# MB_Control.net
KiCad netlist of a schematic drawn in Altium Designer
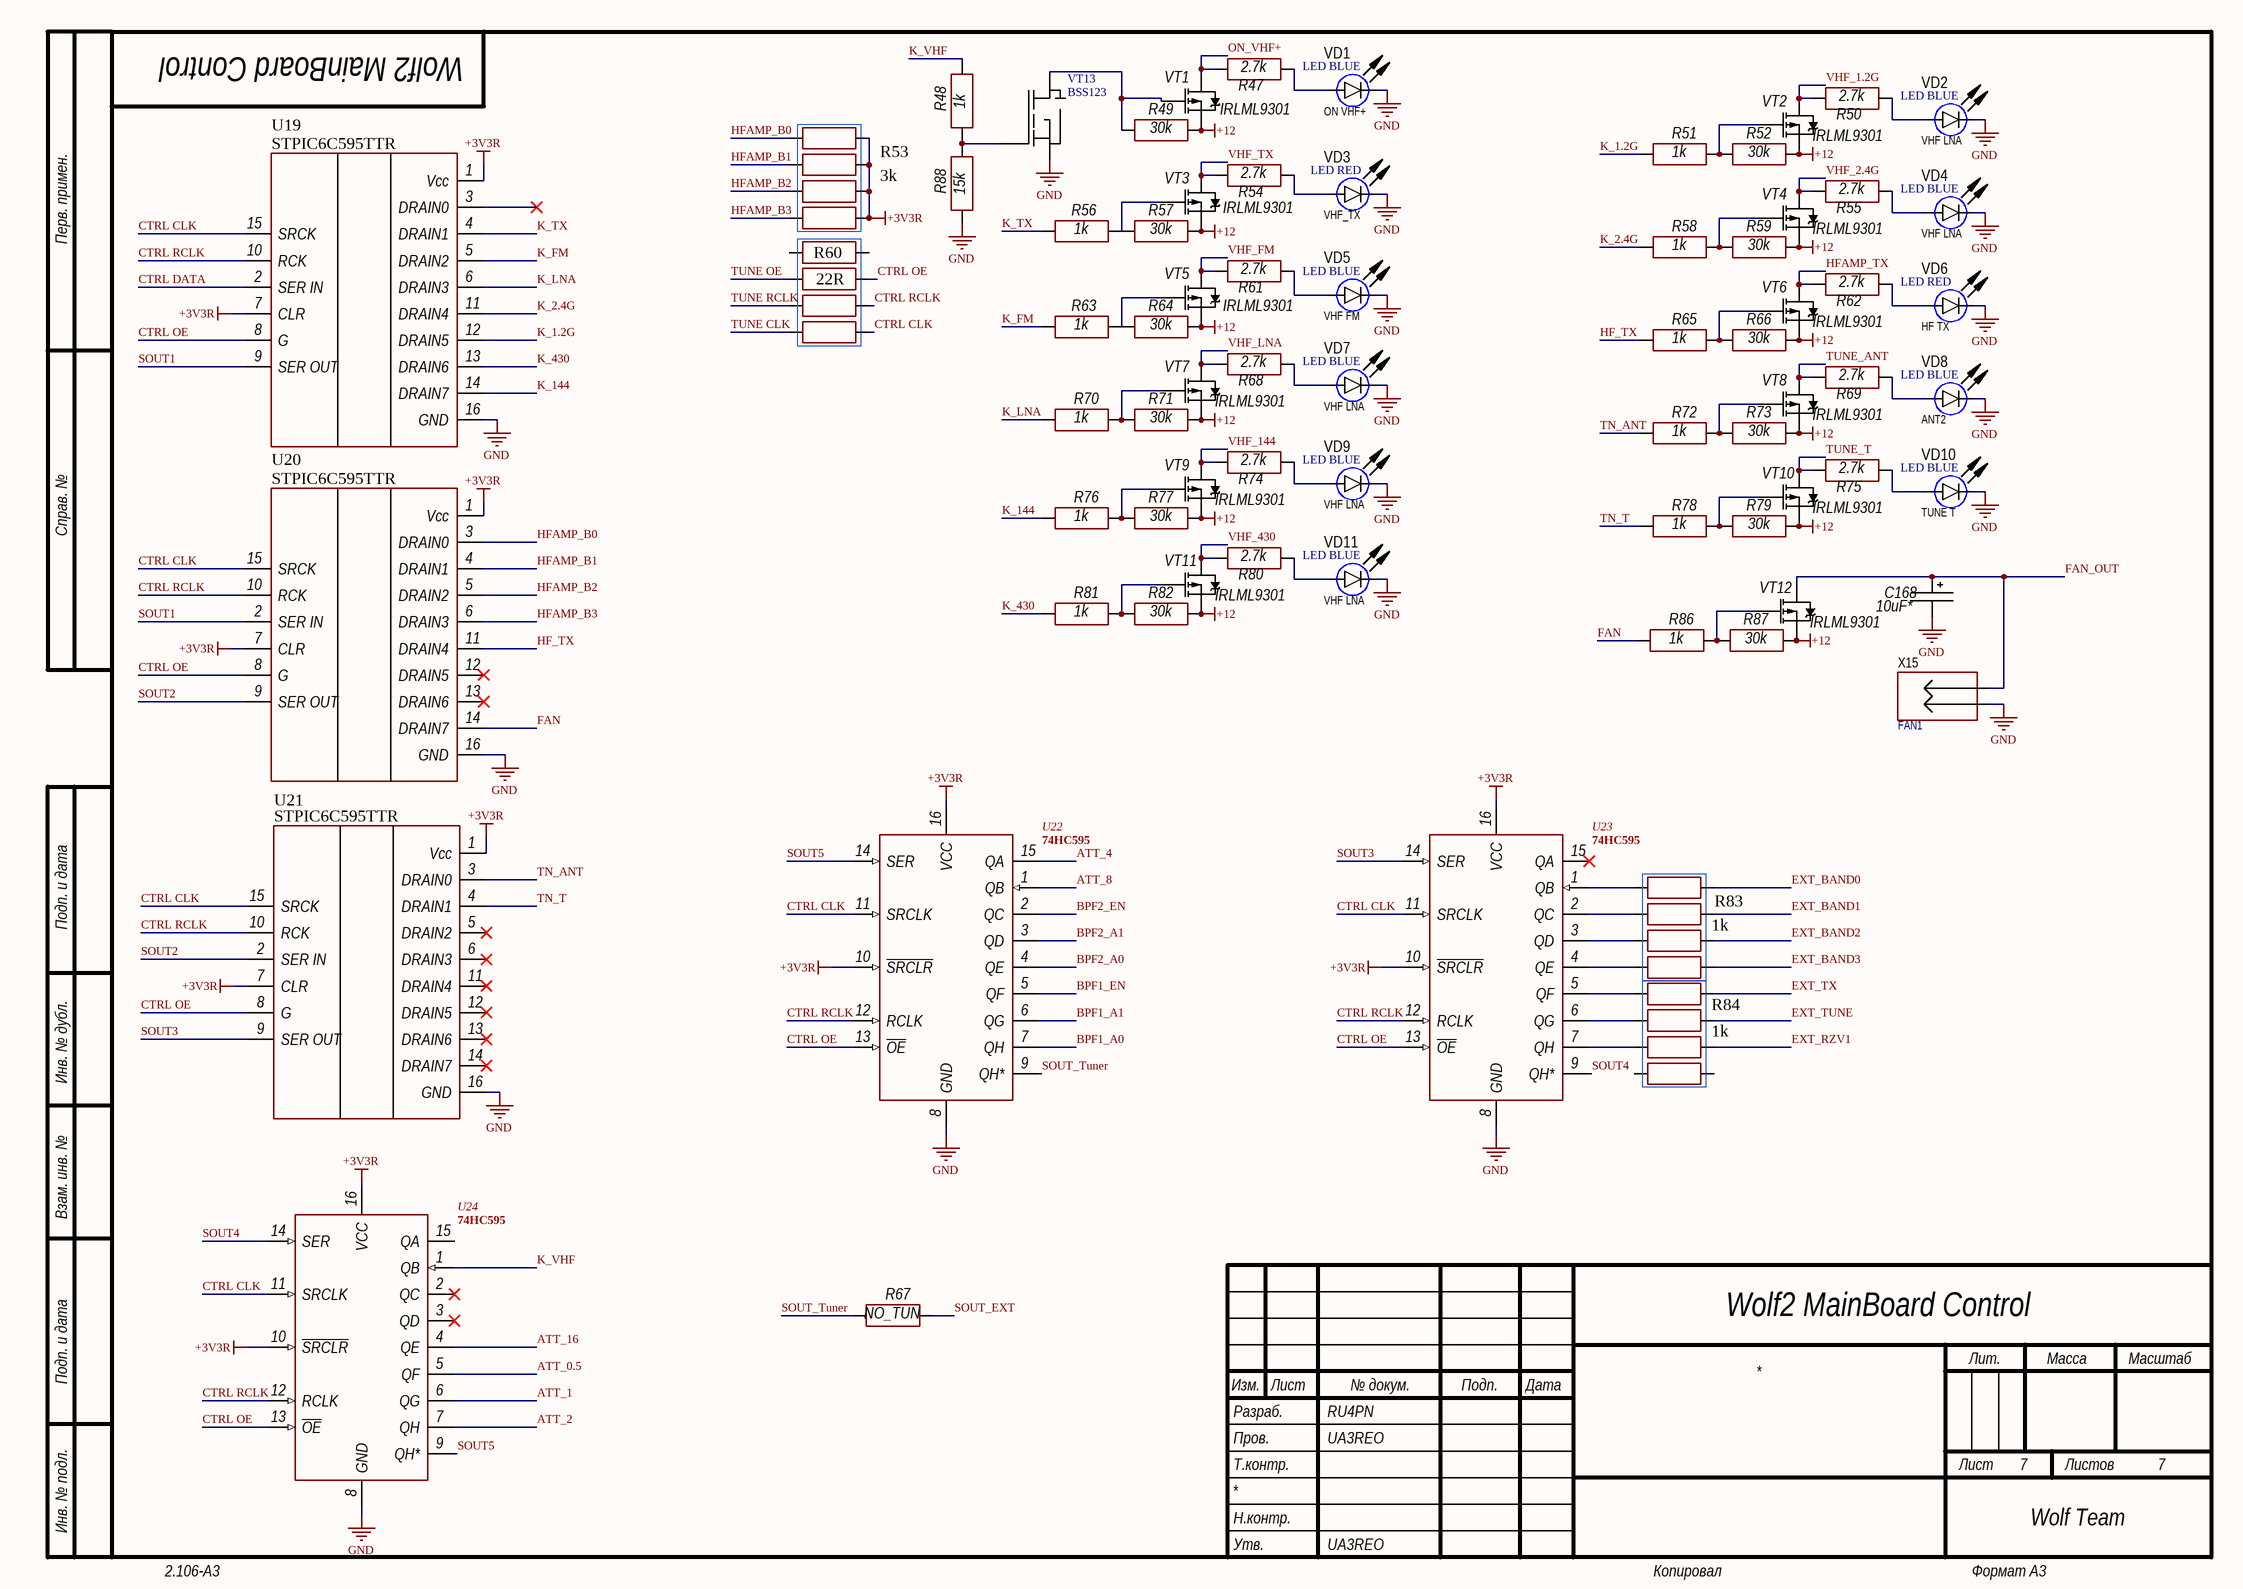
[diagram p0: MB_Control.SchDoc]

(export (version "E")
  (design (tool "Eeschema 10.0.6"))
  (components
    (comp (ref "C168")
      (value "10uF*")
      (footprint "standard:TANTAL_B")
      (libsource (lib "Discrete") (part "TantalCap"))
    )
    (comp (ref "R47")
      (value "2.7k")
      (footprint "standard:CH0805R")
      (libsource (lib "Discrete") (part "Resistor"))
    )
    (comp (ref "R48") (value "1k") (footprint "standard:CH0805R") (libsource (lib "") (part "Resistor_1")))
    (comp (ref "R49")
      (value "30k")
      (footprint "standard:CH0805R")
      (libsource (lib "Discrete") (part "Resistor"))
    )
    (comp (ref "R50")
      (value "2.7k")
      (footprint "standard:CH0805R")
      (libsource (lib "Discrete") (part "Resistor"))
    )
    (comp (ref "R51")
      (value "1k")
      (footprint "standard:CH0805R")
      (libsource (lib "Discrete") (part "Resistor"))
    )
    (comp (ref "R52")
      (value "30k")
      (footprint "standard:CH0805R")
      (libsource (lib "Discrete") (part "Resistor"))
    )
    (comp (ref "R53") (value "3k") (footprint "CAT16") (libsource (lib "Discrete") (part "CAT10-0804")))
    (comp (ref "R54")
      (value "2.7k")
      (footprint "standard:CH0805R")
      (libsource (lib "Discrete") (part "Resistor"))
    )
    (comp (ref "R55")
      (value "2.7k")
      (footprint "standard:CH0805R")
      (libsource (lib "Discrete") (part "Resistor"))
    )
    (comp (ref "R56")
      (value "1k")
      (footprint "standard:CH0805R")
      (libsource (lib "Discrete") (part "Resistor"))
    )
    (comp (ref "R57")
      (value "30k")
      (footprint "standard:CH0805R")
      (libsource (lib "Discrete") (part "Resistor"))
    )
    (comp (ref "R58")
      (value "1k")
      (footprint "standard:CH0805R")
      (libsource (lib "Discrete") (part "Resistor"))
    )
    (comp (ref "R59")
      (value "30k")
      (footprint "standard:CH0805R")
      (libsource (lib "Discrete") (part "Resistor"))
    )
    (comp (ref "R60") (value "22R") (footprint "CAT16") (libsource (lib "") (part "CAT10-0804_1")))
    (comp (ref "R61")
      (value "2.7k")
      (footprint "standard:CH0805R")
      (libsource (lib "Discrete") (part "Resistor"))
    )
    (comp (ref "R62")
      (value "2.7k")
      (footprint "standard:CH0805R")
      (libsource (lib "Discrete") (part "Resistor"))
    )
    (comp (ref "R63")
      (value "1k")
      (footprint "standard:CH0805R")
      (libsource (lib "Discrete") (part "Resistor"))
    )
    (comp (ref "R64")
      (value "30k")
      (footprint "standard:CH0805R")
      (libsource (lib "Discrete") (part "Resistor"))
    )
    (comp (ref "R65")
      (value "1k")
      (footprint "standard:CH0805R")
      (libsource (lib "Discrete") (part "Resistor"))
    )
    (comp (ref "R66")
      (value "30k")
      (footprint "standard:CH0805R")
      (libsource (lib "Discrete") (part "Resistor"))
    )
    (comp (ref "R67")
      (value "NO_TUN")
      (footprint "standard:CH0805R")
      (libsource (lib "Discrete") (part "Resistor"))
    )
    (comp (ref "R68")
      (value "2.7k")
      (footprint "standard:CH0805R")
      (libsource (lib "Discrete") (part "Resistor"))
    )
    (comp (ref "R69")
      (value "2.7k")
      (footprint "standard:CH0805R")
      (libsource (lib "Discrete") (part "Resistor"))
    )
    (comp (ref "R70")
      (value "1k")
      (footprint "standard:CH0805R")
      (libsource (lib "Discrete") (part "Resistor"))
    )
    (comp (ref "R71")
      (value "30k")
      (footprint "standard:CH0805R")
      (libsource (lib "Discrete") (part "Resistor"))
    )
    (comp (ref "R72")
      (value "1k")
      (footprint "standard:CH0805R")
      (libsource (lib "Discrete") (part "Resistor"))
    )
    (comp (ref "R73")
      (value "30k")
      (footprint "standard:CH0805R")
      (libsource (lib "Discrete") (part "Resistor"))
    )
    (comp (ref "R74")
      (value "2.7k")
      (footprint "standard:CH0805R")
      (libsource (lib "Discrete") (part "Resistor"))
    )
    (comp (ref "R75")
      (value "2.7k")
      (footprint "standard:CH0805R")
      (libsource (lib "Discrete") (part "Resistor"))
    )
    (comp (ref "R76")
      (value "1k")
      (footprint "standard:CH0805R")
      (libsource (lib "Discrete") (part "Resistor"))
    )
    (comp (ref "R77")
      (value "30k")
      (footprint "standard:CH0805R")
      (libsource (lib "Discrete") (part "Resistor"))
    )
    (comp (ref "R78")
      (value "1k")
      (footprint "standard:CH0805R")
      (libsource (lib "Discrete") (part "Resistor"))
    )
    (comp (ref "R79")
      (value "30k")
      (footprint "standard:CH0805R")
      (libsource (lib "Discrete") (part "Resistor"))
    )
    (comp (ref "R80")
      (value "2.7k")
      (footprint "standard:CH0805R")
      (libsource (lib "Discrete") (part "Resistor"))
    )
    (comp (ref "R81")
      (value "1k")
      (footprint "standard:CH0805R")
      (libsource (lib "Discrete") (part "Resistor"))
    )
    (comp (ref "R82")
      (value "30k")
      (footprint "standard:CH0805R")
      (libsource (lib "Discrete") (part "Resistor"))
    )
    (comp (ref "R83") (value "1k") (footprint "CAT16") (libsource (lib "Discrete") (part "CAT10-0804")))
    (comp (ref "R84") (value "1k") (footprint "CAT16") (libsource (lib "Discrete") (part "CAT10-0804")))
    (comp (ref "R86")
      (value "1k")
      (footprint "standard:CH0805R")
      (libsource (lib "Discrete") (part "Resistor"))
    )
    (comp (ref "R87")
      (value "30k")
      (footprint "standard:CH0805R")
      (libsource (lib "Discrete") (part "Resistor"))
    )
    (comp (ref "R88") (value "15k") (footprint "standard:CH0805R") (libsource (lib "") (part "Resistor_1")))
    (comp (ref "U19")
      (value "STPIC6C595TTR")
      (footprint "16-TSOP")
      (libsource (lib "") (part "STPIC6C595TTR_1"))
    )
    (comp (ref "U20")
      (value "STPIC6C595TTR")
      (footprint "16-TSOP")
      (libsource (lib "Digital") (part "STPIC6C595TTR"))
    )
    (comp (ref "U21")
      (value "STPIC6C595TTR")
      (footprint "16-TSOP")
      (libsource (lib "Digital") (part "STPIC6C595TTR"))
    )
    (comp (ref "U22") (value "74HC595") (footprint "16-SO") (libsource (lib "Digital") (part "HC595")))
    (comp (ref "U23") (value "74HC595") (footprint "16-SO") (libsource (lib "Digital") (part "HC595")))
    (comp (ref "U24") (value "74HC595") (footprint "16-SO") (libsource (lib "Digital") (part "HC595")))
    (comp (ref "VD1")
      (value "LED BLUE")
      (footprint "StandardCase:LED: 0805B")
      (fields
        (field (name "VALUEMANUFACTURERPARTNUMBER") "LED, *, *, *, -55...+150°C")
        (field (name "COLOR") "ON VHF+")
      )
      (libsource (lib "") (part "LED_single_1"))
    )
    (comp (ref "VD2")
      (value "LED BLUE")
      (footprint "StandardCase:LED: 0805B")
      (fields
        (field (name "VALUEMANUFACTURERPARTNUMBER") "LED, *, *, *, -55...+150°C")
        (field (name "COLOR") "VHF LNA")
      )
      (libsource (lib "Diode") (part "LED_single"))
    )
    (comp (ref "VD3")
      (value "LED RED")
      (footprint "StandardCase:LED: 0805R")
      (fields
        (field (name "VALUEMANUFACTURERPARTNUMBER") "LED, *, *, *, -55...+150°C")
        (field (name "COLOR") "VHF_TX")
      )
      (libsource (lib "") (part "LED_single_1"))
    )
    (comp (ref "VD4")
      (value "LED BLUE")
      (footprint "StandardCase:LED: 0805B")
      (fields
        (field (name "VALUEMANUFACTURERPARTNUMBER") "LED, *, *, *, -55...+150°C")
        (field (name "COLOR") "VHF LNA")
      )
      (libsource (lib "Diode") (part "LED_single"))
    )
    (comp (ref "VD5")
      (value "LED BLUE")
      (footprint "StandardCase:LED: 0805B")
      (fields
        (field (name "VALUEMANUFACTURERPARTNUMBER") "LED, *, *, *, -55...+150°C")
        (field (name "COLOR") "VHF FM")
      )
      (libsource (lib "") (part "LED_single_1"))
    )
    (comp (ref "VD6")
      (value "LED RED")
      (footprint "StandardCase:LED: 0805R")
      (fields
        (field (name "VALUEMANUFACTURERPARTNUMBER") "LED, *, *, *, -55...+150°C")
        (field (name "COLOR") "HF TX")
      )
      (libsource (lib "") (part "LED_single_2"))
    )
    (comp (ref "VD7")
      (value "LED BLUE")
      (footprint "StandardCase:LED: 0805B")
      (fields
        (field (name "VALUEMANUFACTURERPARTNUMBER") "LED, *, *, *, -55...+150°C")
        (field (name "COLOR") "VHF LNA")
      )
      (libsource (lib "") (part "LED_single_1"))
    )
    (comp (ref "VD8")
      (value "LED BLUE")
      (footprint "StandardCase:LED: 0805B")
      (fields
        (field (name "VALUEMANUFACTURERPARTNUMBER") "LED, *, *, *, -55...+150°C")
        (field (name "COLOR") "ANT2")
      )
      (libsource (lib "Diode") (part "LED_single"))
    )
    (comp (ref "VD9")
      (value "LED BLUE")
      (footprint "StandardCase:LED: 0805B")
      (fields
        (field (name "VALUEMANUFACTURERPARTNUMBER") "LED, *, *, *, -55...+150°C")
        (field (name "COLOR") "VHF LNA")
      )
      (libsource (lib "") (part "LED_single_1"))
    )
    (comp (ref "VD10")
      (value "LED BLUE")
      (footprint "StandardCase:LED: 0805B")
      (fields
        (field (name "VALUEMANUFACTURERPARTNUMBER") "LED, *, *, *, -55...+150°C")
        (field (name "COLOR") "TUNE T")
      )
      (libsource (lib "Diode") (part "LED_single"))
    )
    (comp (ref "VD11")
      (value "LED BLUE")
      (footprint "StandardCase:LED: 0805B")
      (fields
        (field (name "VALUEMANUFACTURERPARTNUMBER") "LED, *, *, *, -55...+150°C")
        (field (name "COLOR") "VHF LNA")
      )
      (libsource (lib "") (part "LED_single_1"))
    )
    (comp (ref "VT1")
      (value "IRLML9301")
      (footprint "standard:SOT23_132")
      (description "Mosfet")
      (libsource (lib "Transistor") (part "IRLML9301"))
    )
    (comp (ref "VT2")
      (value "IRLML9301")
      (footprint "standard:SOT23_132")
      (description "Mosfet")
      (libsource (lib "") (part "IRLML9301_1"))
    )
    (comp (ref "VT3")
      (value "IRLML9301")
      (footprint "standard:SOT23_132")
      (description "Mosfet")
      (libsource (lib "Transistor") (part "IRLML9301"))
    )
    (comp (ref "VT4")
      (value "IRLML9301")
      (footprint "standard:SOT23_132")
      (description "Mosfet")
      (libsource (lib "") (part "IRLML9301_1"))
    )
    (comp (ref "VT5")
      (value "IRLML9301")
      (footprint "standard:SOT23_132")
      (description "Mosfet")
      (libsource (lib "Transistor") (part "IRLML9301"))
    )
    (comp (ref "VT6")
      (value "IRLML9301")
      (footprint "standard:SOT23_132")
      (description "Mosfet")
      (libsource (lib "") (part "IRLML9301_1"))
    )
    (comp (ref "VT7")
      (value "IRLML9301")
      (footprint "standard:SOT23_132")
      (description "Mosfet")
      (libsource (lib "Transistor") (part "IRLML9301"))
    )
    (comp (ref "VT8")
      (value "IRLML9301")
      (footprint "standard:SOT23_132")
      (description "Mosfet")
      (libsource (lib "") (part "IRLML9301_1"))
    )
    (comp (ref "VT9")
      (value "IRLML9301")
      (footprint "standard:SOT23_132")
      (description "Mosfet")
      (libsource (lib "Transistor") (part "IRLML9301"))
    )
    (comp (ref "VT10")
      (value "IRLML9301")
      (footprint "standard:SOT23_132")
      (description "Mosfet")
      (libsource (lib "") (part "IRLML9301_1"))
    )
    (comp (ref "VT11")
      (value "IRLML9301")
      (footprint "standard:SOT23_132")
      (description "Mosfet")
      (libsource (lib "Transistor") (part "IRLML9301"))
    )
    (comp (ref "VT12")
      (value "IRLML9301")
      (footprint "standard:SOT23_132")
      (description "Mosfet")
      (libsource (lib "") (part "IRLML9301_1"))
    )
    (comp (ref "VT13")
      (value "BSS123")
      (footprint "SOT23_132")
      (libsource (lib "Transistor") (part "BSS123"))
    )
    (comp (ref "X15")
      (value "FAN1")
      (footprint "CON: CWF-2")
      (libsource (lib "Connectors") (part "Component-2pin"))
    )
  )
  (nets
    (net (code "1") (name "+3V3R") (class "Default")
      (node (ref "R53") (pin "5") (pinfunction "5_5") (pintype "passive"))
      (node (ref "R53") (pin "6") (pinfunction "6_6") (pintype "passive"))
      (node (ref "R53") (pin "7") (pinfunction "7_7") (pintype "passive"))
      (node (ref "R53") (pin "8") (pinfunction "8_8") (pintype "passive"))
      (node (ref "U19") (pin "1") (pinfunction "Vcc_1") (pintype "passive"))
      (node (ref "U19") (pin "7") (pinfunction "CLR_7") (pintype "passive"))
      (node (ref "U20") (pin "1") (pinfunction "Vcc_1") (pintype "passive"))
      (node (ref "U20") (pin "7") (pinfunction "CLR_7") (pintype "passive"))
      (node (ref "U21") (pin "1") (pinfunction "Vcc_1") (pintype "passive"))
      (node (ref "U21") (pin "7") (pinfunction "CLR_7") (pintype "passive"))
      (node (ref "U22") (pin "10") (pinfunction "~{SRCLR}_10") (pintype "input"))
      (node (ref "U22") (pin "16") (pinfunction "VCC_16") (pintype "passive"))
      (node (ref "U23") (pin "10") (pinfunction "~{SRCLR}_10") (pintype "input"))
      (node (ref "U23") (pin "16") (pinfunction "VCC_16") (pintype "passive"))
      (node (ref "U24") (pin "10") (pinfunction "~{SRCLR}_10") (pintype "input"))
      (node (ref "U24") (pin "16") (pinfunction "VCC_16") (pintype "passive"))
    )
    (net (code "2") (name "+12") (class "Default")
      (node (ref "R49") (pin "1") (pinfunction "1_1") (pintype "passive"))
      (node (ref "R52") (pin "1") (pinfunction "1_1") (pintype "passive"))
      (node (ref "R57") (pin "1") (pinfunction "1_1") (pintype "passive"))
      (node (ref "R59") (pin "1") (pinfunction "1_1") (pintype "passive"))
      (node (ref "R64") (pin "1") (pinfunction "1_1") (pintype "passive"))
      (node (ref "R66") (pin "1") (pinfunction "1_1") (pintype "passive"))
      (node (ref "R71") (pin "1") (pinfunction "1_1") (pintype "passive"))
      (node (ref "R73") (pin "1") (pinfunction "1_1") (pintype "passive"))
      (node (ref "R77") (pin "1") (pinfunction "1_1") (pintype "passive"))
      (node (ref "R79") (pin "1") (pinfunction "1_1") (pintype "passive"))
      (node (ref "R82") (pin "1") (pinfunction "1_1") (pintype "passive"))
      (node (ref "R87") (pin "1") (pinfunction "1_1") (pintype "passive"))
      (node (ref "VT1") (pin "2") (pinfunction "S_2") (pintype "passive"))
      (node (ref "VT10") (pin "2") (pinfunction "S_2") (pintype "passive"))
      (node (ref "VT11") (pin "2") (pinfunction "S_2") (pintype "passive"))
      (node (ref "VT12") (pin "2") (pinfunction "S_2") (pintype "passive"))
      (node (ref "VT2") (pin "2") (pinfunction "S_2") (pintype "passive"))
      (node (ref "VT3") (pin "2") (pinfunction "S_2") (pintype "passive"))
      (node (ref "VT4") (pin "2") (pinfunction "S_2") (pintype "passive"))
      (node (ref "VT5") (pin "2") (pinfunction "S_2") (pintype "passive"))
      (node (ref "VT6") (pin "2") (pinfunction "S_2") (pintype "passive"))
      (node (ref "VT7") (pin "2") (pinfunction "S_2") (pintype "passive"))
      (node (ref "VT8") (pin "2") (pinfunction "S_2") (pintype "passive"))
      (node (ref "VT9") (pin "2") (pinfunction "S_2") (pintype "passive"))
    )
    (net (code "3") (name "/ATT_0.5") (class "Default")
      (node (ref "U24") (pin "5") (pinfunction "QF_5") (pintype "passive"))
    )
    (net (code "4") (name "/ATT_1") (class "Default")
      (node (ref "U24") (pin "6") (pinfunction "QG_6") (pintype "passive"))
    )
    (net (code "5") (name "/ATT_2") (class "Default")
      (node (ref "U24") (pin "7") (pinfunction "QH_7") (pintype "passive"))
    )
    (net (code "6") (name "/ATT_4") (class "Default")
      (node (ref "U22") (pin "15") (pinfunction "QA_15") (pintype "passive"))
    )
    (net (code "7") (name "/ATT_8") (class "Default")
      (node (ref "U22") (pin "1") (pinfunction "QB_1") (pintype "input"))
    )
    (net (code "8") (name "/ATT_16") (class "Default")
      (node (ref "U24") (pin "4") (pinfunction "QE_4") (pintype "passive"))
    )
    (net (code "9") (name "/BPF1_A0") (class "Default")
      (node (ref "U22") (pin "7") (pinfunction "QH_7") (pintype "passive"))
    )
    (net (code "10") (name "/BPF1_A1") (class "Default")
      (node (ref "U22") (pin "6") (pinfunction "QG_6") (pintype "passive"))
    )
    (net (code "11") (name "/BPF1_EN") (class "Default")
      (node (ref "U22") (pin "5") (pinfunction "QF_5") (pintype "passive"))
    )
    (net (code "12") (name "/BPF2_A0") (class "Default")
      (node (ref "U22") (pin "4") (pinfunction "QE_4") (pintype "passive"))
    )
    (net (code "13") (name "/BPF2_A1") (class "Default")
      (node (ref "U22") (pin "3") (pinfunction "QD_3") (pintype "passive"))
    )
    (net (code "14") (name "/BPF2_EN") (class "Default")
      (node (ref "U22") (pin "2") (pinfunction "QC_2") (pintype "passive"))
    )
    (net (code "15") (name "/CTRL CLK") (class "Default")
      (node (ref "R60") (pin "8") (pinfunction "8_8") (pintype "passive"))
      (node (ref "U19") (pin "15") (pinfunction "SRCK_15") (pintype "passive"))
      (node (ref "U20") (pin "15") (pinfunction "SRCK_15") (pintype "passive"))
      (node (ref "U21") (pin "15") (pinfunction "SRCK_15") (pintype "passive"))
      (node (ref "U22") (pin "11") (pinfunction "SRCLK_11") (pintype "input"))
      (node (ref "U23") (pin "11") (pinfunction "SRCLK_11") (pintype "input"))
      (node (ref "U24") (pin "11") (pinfunction "SRCLK_11") (pintype "input"))
    )
    (net (code "16") (name "/CTRL DATA") (class "Default")
      (node (ref "U19") (pin "2") (pinfunction "SER_IN_2") (pintype "passive"))
    )
    (net (code "17") (name "/CTRL OE") (class "Default")
      (node (ref "R60") (pin "6") (pinfunction "6_6") (pintype "passive"))
      (node (ref "U19") (pin "8") (pinfunction "G_8") (pintype "passive"))
      (node (ref "U20") (pin "8") (pinfunction "G_8") (pintype "passive"))
      (node (ref "U21") (pin "8") (pinfunction "G_8") (pintype "passive"))
      (node (ref "U22") (pin "13") (pinfunction "~{OE}_13") (pintype "input"))
      (node (ref "U23") (pin "13") (pinfunction "~{OE}_13") (pintype "input"))
      (node (ref "U24") (pin "13") (pinfunction "~{OE}_13") (pintype "input"))
    )
    (net (code "18") (name "/CTRL RCLK") (class "Default")
      (node (ref "R60") (pin "7") (pinfunction "7_7") (pintype "passive"))
      (node (ref "U19") (pin "10") (pinfunction "RCK_10") (pintype "passive"))
      (node (ref "U20") (pin "10") (pinfunction "RCK_10") (pintype "passive"))
      (node (ref "U21") (pin "10") (pinfunction "RCK_10") (pintype "passive"))
      (node (ref "U22") (pin "12") (pinfunction "RCLK_12") (pintype "input"))
      (node (ref "U23") (pin "12") (pinfunction "RCLK_12") (pintype "input"))
      (node (ref "U24") (pin "12") (pinfunction "RCLK_12") (pintype "input"))
    )
    (net (code "19") (name "/EXT_BAND0") (class "Default")
      (node (ref "R83") (pin "5") (pinfunction "5_5") (pintype "passive"))
    )
    (net (code "20") (name "/EXT_BAND1") (class "Default")
      (node (ref "R83") (pin "6") (pinfunction "6_6") (pintype "passive"))
    )
    (net (code "21") (name "/EXT_BAND2") (class "Default")
      (node (ref "R83") (pin "7") (pinfunction "7_7") (pintype "passive"))
    )
    (net (code "22") (name "/EXT_BAND3") (class "Default")
      (node (ref "R83") (pin "8") (pinfunction "8_8") (pintype "passive"))
    )
    (net (code "23") (name "/EXT_RZV1") (class "Default")
      (node (ref "R84") (pin "7") (pinfunction "7_7") (pintype "passive"))
    )
    (net (code "24") (name "/EXT_TUNE") (class "Default")
      (node (ref "R84") (pin "6") (pinfunction "6_6") (pintype "passive"))
    )
    (net (code "25") (name "/EXT_TX") (class "Default")
      (node (ref "R84") (pin "5") (pinfunction "5_5") (pintype "passive"))
    )
    (net (code "26") (name "/FAN") (class "Default")
      (node (ref "R86") (pin "2") (pinfunction "2_2") (pintype "passive"))
      (node (ref "U20") (pin "14") (pinfunction "DRAIN7_14") (pintype "passive"))
    )
    (net (code "27") (name "/FAN_OUT") (class "Default")
      (node (ref "C168") (pin "1") (pinfunction "1_1") (pintype "power_in"))
      (node (ref "VT12") (pin "3") (pinfunction "D_3") (pintype "passive"))
      (node (ref "X15") (pin "1") (pinfunction "1_1") (pintype "passive"))
    )
    (net (code "28") (name "/HFAMP_B0") (class "Default")
      (node (ref "R53") (pin "1") (pinfunction "1_1") (pintype "passive"))
      (node (ref "U20") (pin "3") (pinfunction "DRAIN0_3") (pintype "passive"))
    )
    (net (code "29") (name "/HFAMP_B1") (class "Default")
      (node (ref "R53") (pin "2") (pinfunction "2_2") (pintype "passive"))
      (node (ref "U20") (pin "4") (pinfunction "DRAIN1_4") (pintype "passive"))
    )
    (net (code "30") (name "/HFAMP_B2") (class "Default")
      (node (ref "R53") (pin "3") (pinfunction "3_3") (pintype "passive"))
      (node (ref "U20") (pin "5") (pinfunction "DRAIN2_5") (pintype "passive"))
    )
    (net (code "31") (name "/HFAMP_B3") (class "Default")
      (node (ref "R53") (pin "4") (pinfunction "4_4") (pintype "passive"))
      (node (ref "U20") (pin "6") (pinfunction "DRAIN3_6") (pintype "passive"))
    )
    (net (code "32") (name "/HFAMP_TX") (class "Default")
      (node (ref "R62") (pin "2") (pinfunction "2_2") (pintype "passive"))
      (node (ref "VT6") (pin "3") (pinfunction "D_3") (pintype "passive"))
    )
    (net (code "33") (name "/HF_TX") (class "Default")
      (node (ref "R65") (pin "2") (pinfunction "2_2") (pintype "passive"))
      (node (ref "U20") (pin "11") (pinfunction "DRAIN4_11") (pintype "passive"))
    )
    (net (code "34") (name "/K_1.2G") (class "Default")
      (node (ref "R51") (pin "2") (pinfunction "2_2") (pintype "passive"))
      (node (ref "U19") (pin "12") (pinfunction "DRAIN5_12") (pintype "passive"))
    )
    (net (code "35") (name "/K_2.4G") (class "Default")
      (node (ref "R58") (pin "2") (pinfunction "2_2") (pintype "passive"))
      (node (ref "U19") (pin "11") (pinfunction "DRAIN4_11") (pintype "passive"))
    )
    (net (code "36") (name "/K_144") (class "Default")
      (node (ref "R76") (pin "2") (pinfunction "2_2") (pintype "passive"))
      (node (ref "U19") (pin "14") (pinfunction "DRAIN7_14") (pintype "passive"))
    )
    (net (code "37") (name "/K_430") (class "Default")
      (node (ref "R81") (pin "2") (pinfunction "2_2") (pintype "passive"))
      (node (ref "U19") (pin "13") (pinfunction "DRAIN6_13") (pintype "passive"))
    )
    (net (code "38") (name "/K_FM") (class "Default")
      (node (ref "R63") (pin "2") (pinfunction "2_2") (pintype "passive"))
      (node (ref "U19") (pin "5") (pinfunction "DRAIN2_5") (pintype "passive"))
    )
    (net (code "39") (name "/K_LNA") (class "Default")
      (node (ref "R70") (pin "2") (pinfunction "2_2") (pintype "passive"))
      (node (ref "U19") (pin "6") (pinfunction "DRAIN3_6") (pintype "passive"))
    )
    (net (code "40") (name "/K_TX") (class "Default")
      (node (ref "R56") (pin "2") (pinfunction "2_2") (pintype "passive"))
      (node (ref "U19") (pin "4") (pinfunction "DRAIN1_4") (pintype "passive"))
    )
    (net (code "41") (name "/K_VHF") (class "Default")
      (node (ref "R48") (pin "1") (pinfunction "1_1") (pintype "passive"))
      (node (ref "U24") (pin "1") (pinfunction "QB_1") (pintype "input"))
    )
    (net (code "42") (name "/ON_VHF+") (class "Default")
      (node (ref "R47") (pin "2") (pinfunction "2_2") (pintype "passive"))
      (node (ref "VT1") (pin "3") (pinfunction "D_3") (pintype "passive"))
    )
    (net (code "43") (name "/SOUT1") (class "Default")
      (node (ref "U19") (pin "9") (pinfunction "SER_OUT_9") (pintype "passive"))
      (node (ref "U20") (pin "2") (pinfunction "SER_IN_2") (pintype "passive"))
    )
    (net (code "44") (name "/SOUT2") (class "Default")
      (node (ref "U20") (pin "9") (pinfunction "SER_OUT_9") (pintype "passive"))
      (node (ref "U21") (pin "2") (pinfunction "SER_IN_2") (pintype "passive"))
    )
    (net (code "45") (name "/SOUT3") (class "Default")
      (node (ref "U21") (pin "9") (pinfunction "SER_OUT_9") (pintype "passive"))
      (node (ref "U23") (pin "14") (pinfunction "SER_14") (pintype "input"))
    )
    (net (code "46") (name "/SOUT4") (class "Default")
      (node (ref "U23") (pin "9") (pinfunction "QH*_9") (pintype "passive"))
      (node (ref "U24") (pin "14") (pinfunction "SER_14") (pintype "input"))
    )
    (net (code "47") (name "/SOUT5") (class "Default")
      (node (ref "U22") (pin "14") (pinfunction "SER_14") (pintype "input"))
      (node (ref "U24") (pin "9") (pinfunction "QH*_9") (pintype "passive"))
    )
    (net (code "48") (name "/SOUT_EXT") (class "Default")
      (node (ref "R67") (pin "1") (pinfunction "1_1") (pintype "passive"))
    )
    (net (code "49") (name "/SOUT_Tuner") (class "Default")
      (node (ref "R67") (pin "2") (pinfunction "2_2") (pintype "passive"))
      (node (ref "U22") (pin "9") (pinfunction "QH*_9") (pintype "passive"))
    )
    (net (code "50") (name "/TN_ANT") (class "Default")
      (node (ref "R72") (pin "2") (pinfunction "2_2") (pintype "passive"))
      (node (ref "U21") (pin "3") (pinfunction "DRAIN0_3") (pintype "passive"))
    )
    (net (code "51") (name "/TN_T") (class "Default")
      (node (ref "R78") (pin "2") (pinfunction "2_2") (pintype "passive"))
      (node (ref "U21") (pin "4") (pinfunction "DRAIN1_4") (pintype "passive"))
    )
    (net (code "52") (name "/TUNE CLK") (class "Default")
      (node (ref "R60") (pin "4") (pinfunction "4_4") (pintype "passive"))
    )
    (net (code "53") (name "/TUNE OE") (class "Default")
      (node (ref "R60") (pin "2") (pinfunction "2_2") (pintype "passive"))
    )
    (net (code "54") (name "/TUNE RCLK") (class "Default")
      (node (ref "R60") (pin "3") (pinfunction "3_3") (pintype "passive"))
    )
    (net (code "55") (name "/TUNE_ANT") (class "Default")
      (node (ref "R69") (pin "2") (pinfunction "2_2") (pintype "passive"))
      (node (ref "VT8") (pin "3") (pinfunction "D_3") (pintype "passive"))
    )
    (net (code "56") (name "/TUNE_T") (class "Default")
      (node (ref "R75") (pin "2") (pinfunction "2_2") (pintype "passive"))
      (node (ref "VT10") (pin "3") (pinfunction "D_3") (pintype "passive"))
    )
    (net (code "57") (name "/VHF_1.2G") (class "Default")
      (node (ref "R50") (pin "2") (pinfunction "2_2") (pintype "passive"))
      (node (ref "VT2") (pin "3") (pinfunction "D_3") (pintype "passive"))
    )
    (net (code "58") (name "/VHF_2.4G") (class "Default")
      (node (ref "R55") (pin "2") (pinfunction "2_2") (pintype "passive"))
      (node (ref "VT4") (pin "3") (pinfunction "D_3") (pintype "passive"))
    )
    (net (code "59") (name "/VHF_144") (class "Default")
      (node (ref "R74") (pin "2") (pinfunction "2_2") (pintype "passive"))
      (node (ref "VT9") (pin "3") (pinfunction "D_3") (pintype "passive"))
    )
    (net (code "60") (name "/VHF_430") (class "Default")
      (node (ref "R80") (pin "2") (pinfunction "2_2") (pintype "passive"))
      (node (ref "VT11") (pin "3") (pinfunction "D_3") (pintype "passive"))
    )
    (net (code "61") (name "/VHF_FM") (class "Default")
      (node (ref "R61") (pin "2") (pinfunction "2_2") (pintype "passive"))
      (node (ref "VT5") (pin "3") (pinfunction "D_3") (pintype "passive"))
    )
    (net (code "62") (name "/VHF_LNA") (class "Default")
      (node (ref "R68") (pin "2") (pinfunction "2_2") (pintype "passive"))
      (node (ref "VT7") (pin "3") (pinfunction "D_3") (pintype "passive"))
    )
    (net (code "63") (name "/VHF_TX") (class "Default")
      (node (ref "R54") (pin "2") (pinfunction "2_2") (pintype "passive"))
      (node (ref "VT3") (pin "3") (pinfunction "D_3") (pintype "passive"))
    )
    (net (code "64") (name "GND") (class "Default")
      (node (ref "C168") (pin "2") (pinfunction "2_2") (pintype "power_in"))
      (node (ref "R88") (pin "2") (pinfunction "2_2") (pintype "passive"))
      (node (ref "U19") (pin "16") (pinfunction "GND_16") (pintype "passive"))
      (node (ref "U20") (pin "16") (pinfunction "GND_16") (pintype "passive"))
      (node (ref "U21") (pin "16") (pinfunction "GND_16") (pintype "passive"))
      (node (ref "U22") (pin "8") (pinfunction "GND_8") (pintype "passive"))
      (node (ref "U23") (pin "8") (pinfunction "GND_8") (pintype "passive"))
      (node (ref "U24") (pin "8") (pinfunction "GND_8") (pintype "passive"))
      (node (ref "VD1") (pin "2") (pinfunction "C_2") (pintype "passive"))
      (node (ref "VD10") (pin "2") (pinfunction "C_2") (pintype "passive"))
      (node (ref "VD11") (pin "2") (pinfunction "C_2") (pintype "passive"))
      (node (ref "VD2") (pin "2") (pinfunction "C_2") (pintype "passive"))
      (node (ref "VD3") (pin "2") (pinfunction "C_2") (pintype "passive"))
      (node (ref "VD4") (pin "2") (pinfunction "C_2") (pintype "passive"))
      (node (ref "VD5") (pin "2") (pinfunction "C_2") (pintype "passive"))
      (node (ref "VD6") (pin "2") (pinfunction "C_2") (pintype "passive"))
      (node (ref "VD7") (pin "2") (pinfunction "C_2") (pintype "passive"))
      (node (ref "VD8") (pin "2") (pinfunction "C_2") (pintype "passive"))
      (node (ref "VD9") (pin "2") (pinfunction "C_2") (pintype "passive"))
      (node (ref "VT13") (pin "2") (pinfunction "S_2") (pintype "passive"))
      (node (ref "X15") (pin "2") (pinfunction "2_2") (pintype "passive"))
    )
    (net (code "65") (name "Net-(U23-QB)") (class "Default")
      (node (ref "R83") (pin "1") (pinfunction "1_1") (pintype "passive"))
      (node (ref "U23") (pin "1") (pinfunction "QB_1") (pintype "input"))
    )
    (net (code "66") (name "Net-(U23-QC)") (class "Default")
      (node (ref "R83") (pin "2") (pinfunction "2_2") (pintype "passive"))
      (node (ref "U23") (pin "2") (pinfunction "QC_2") (pintype "passive"))
    )
    (net (code "67") (name "Net-(U23-QD)") (class "Default")
      (node (ref "R83") (pin "3") (pinfunction "3_3") (pintype "passive"))
      (node (ref "U23") (pin "3") (pinfunction "QD_3") (pintype "passive"))
    )
    (net (code "68") (name "Net-(U23-QE)") (class "Default")
      (node (ref "R83") (pin "4") (pinfunction "4_4") (pintype "passive"))
      (node (ref "U23") (pin "4") (pinfunction "QE_4") (pintype "passive"))
    )
    (net (code "69") (name "Net-(U23-QF)") (class "Default")
      (node (ref "R84") (pin "1") (pinfunction "1_1") (pintype "passive"))
      (node (ref "U23") (pin "5") (pinfunction "QF_5") (pintype "passive"))
    )
    (net (code "70") (name "Net-(U23-QG)") (class "Default")
      (node (ref "R84") (pin "2") (pinfunction "2_2") (pintype "passive"))
      (node (ref "U23") (pin "6") (pinfunction "QG_6") (pintype "passive"))
    )
    (net (code "71") (name "Net-(U23-QH)") (class "Default")
      (node (ref "R84") (pin "3") (pinfunction "3_3") (pintype "passive"))
      (node (ref "U23") (pin "7") (pinfunction "QH_7") (pintype "passive"))
    )
    (net (code "72") (name "Net-(VD1-A)") (class "Default")
      (node (ref "R47") (pin "1") (pinfunction "1_1") (pintype "passive"))
      (node (ref "VD1") (pin "1") (pinfunction "A_1") (pintype "passive"))
    )
    (net (code "73") (name "Net-(VD2-A)") (class "Default")
      (node (ref "R50") (pin "1") (pinfunction "1_1") (pintype "passive"))
      (node (ref "VD2") (pin "1") (pinfunction "A_1") (pintype "passive"))
    )
    (net (code "74") (name "Net-(VD3-A)") (class "Default")
      (node (ref "R54") (pin "1") (pinfunction "1_1") (pintype "passive"))
      (node (ref "VD3") (pin "1") (pinfunction "A_1") (pintype "passive"))
    )
    (net (code "75") (name "Net-(VD4-A)") (class "Default")
      (node (ref "R55") (pin "1") (pinfunction "1_1") (pintype "passive"))
      (node (ref "VD4") (pin "1") (pinfunction "A_1") (pintype "passive"))
    )
    (net (code "76") (name "Net-(VD5-A)") (class "Default")
      (node (ref "R61") (pin "1") (pinfunction "1_1") (pintype "passive"))
      (node (ref "VD5") (pin "1") (pinfunction "A_1") (pintype "passive"))
    )
    (net (code "77") (name "Net-(VD6-A)") (class "Default")
      (node (ref "R62") (pin "1") (pinfunction "1_1") (pintype "passive"))
      (node (ref "VD6") (pin "1") (pinfunction "A_1") (pintype "passive"))
    )
    (net (code "78") (name "Net-(VD7-A)") (class "Default")
      (node (ref "R68") (pin "1") (pinfunction "1_1") (pintype "passive"))
      (node (ref "VD7") (pin "1") (pinfunction "A_1") (pintype "passive"))
    )
    (net (code "79") (name "Net-(VD8-A)") (class "Default")
      (node (ref "R69") (pin "1") (pinfunction "1_1") (pintype "passive"))
      (node (ref "VD8") (pin "1") (pinfunction "A_1") (pintype "passive"))
    )
    (net (code "80") (name "Net-(VD9-A)") (class "Default")
      (node (ref "R74") (pin "1") (pinfunction "1_1") (pintype "passive"))
      (node (ref "VD9") (pin "1") (pinfunction "A_1") (pintype "passive"))
    )
    (net (code "81") (name "Net-(VD10-A)") (class "Default")
      (node (ref "R75") (pin "1") (pinfunction "1_1") (pintype "passive"))
      (node (ref "VD10") (pin "1") (pinfunction "A_1") (pintype "passive"))
    )
    (net (code "82") (name "Net-(VD11-A)") (class "Default")
      (node (ref "R80") (pin "1") (pinfunction "1_1") (pintype "passive"))
      (node (ref "VD11") (pin "1") (pinfunction "A_1") (pintype "passive"))
    )
    (net (code "83") (name "Net-(VT1-G)") (class "Default")
      (node (ref "R49") (pin "2") (pinfunction "2_2") (pintype "passive"))
      (node (ref "VT1") (pin "1") (pinfunction "G_1") (pintype "passive"))
      (node (ref "VT13") (pin "3") (pinfunction "D_3") (pintype "passive"))
    )
    (net (code "84") (name "Net-(VT2-G)") (class "Default")
      (node (ref "R51") (pin "1") (pinfunction "1_1") (pintype "passive"))
      (node (ref "R52") (pin "2") (pinfunction "2_2") (pintype "passive"))
      (node (ref "VT2") (pin "1") (pinfunction "G_1") (pintype "passive"))
    )
    (net (code "85") (name "Net-(VT3-G)") (class "Default")
      (node (ref "R56") (pin "1") (pinfunction "1_1") (pintype "passive"))
      (node (ref "R57") (pin "2") (pinfunction "2_2") (pintype "passive"))
      (node (ref "VT3") (pin "1") (pinfunction "G_1") (pintype "passive"))
    )
    (net (code "86") (name "Net-(VT4-G)") (class "Default")
      (node (ref "R58") (pin "1") (pinfunction "1_1") (pintype "passive"))
      (node (ref "R59") (pin "2") (pinfunction "2_2") (pintype "passive"))
      (node (ref "VT4") (pin "1") (pinfunction "G_1") (pintype "passive"))
    )
    (net (code "87") (name "Net-(VT5-G)") (class "Default")
      (node (ref "R63") (pin "1") (pinfunction "1_1") (pintype "passive"))
      (node (ref "R64") (pin "2") (pinfunction "2_2") (pintype "passive"))
      (node (ref "VT5") (pin "1") (pinfunction "G_1") (pintype "passive"))
    )
    (net (code "88") (name "Net-(VT6-G)") (class "Default")
      (node (ref "R65") (pin "1") (pinfunction "1_1") (pintype "passive"))
      (node (ref "R66") (pin "2") (pinfunction "2_2") (pintype "passive"))
      (node (ref "VT6") (pin "1") (pinfunction "G_1") (pintype "passive"))
    )
    (net (code "89") (name "Net-(VT7-G)") (class "Default")
      (node (ref "R70") (pin "1") (pinfunction "1_1") (pintype "passive"))
      (node (ref "R71") (pin "2") (pinfunction "2_2") (pintype "passive"))
      (node (ref "VT7") (pin "1") (pinfunction "G_1") (pintype "passive"))
    )
    (net (code "90") (name "Net-(VT8-G)") (class "Default")
      (node (ref "R72") (pin "1") (pinfunction "1_1") (pintype "passive"))
      (node (ref "R73") (pin "2") (pinfunction "2_2") (pintype "passive"))
      (node (ref "VT8") (pin "1") (pinfunction "G_1") (pintype "passive"))
    )
    (net (code "91") (name "Net-(VT9-G)") (class "Default")
      (node (ref "R76") (pin "1") (pinfunction "1_1") (pintype "passive"))
      (node (ref "R77") (pin "2") (pinfunction "2_2") (pintype "passive"))
      (node (ref "VT9") (pin "1") (pinfunction "G_1") (pintype "passive"))
    )
    (net (code "92") (name "Net-(VT10-G)") (class "Default")
      (node (ref "R78") (pin "1") (pinfunction "1_1") (pintype "passive"))
      (node (ref "R79") (pin "2") (pinfunction "2_2") (pintype "passive"))
      (node (ref "VT10") (pin "1") (pinfunction "G_1") (pintype "passive"))
    )
    (net (code "93") (name "Net-(VT11-G)") (class "Default")
      (node (ref "R81") (pin "1") (pinfunction "1_1") (pintype "passive"))
      (node (ref "R82") (pin "2") (pinfunction "2_2") (pintype "passive"))
      (node (ref "VT11") (pin "1") (pinfunction "G_1") (pintype "passive"))
    )
    (net (code "94") (name "Net-(VT12-G)") (class "Default")
      (node (ref "R86") (pin "1") (pinfunction "1_1") (pintype "passive"))
      (node (ref "R87") (pin "2") (pinfunction "2_2") (pintype "passive"))
      (node (ref "VT12") (pin "1") (pinfunction "G_1") (pintype "passive"))
    )
    (net (code "95") (name "Net-(VT13-G)") (class "Default")
      (node (ref "R48") (pin "2") (pinfunction "2_2") (pintype "passive"))
      (node (ref "R88") (pin "1") (pinfunction "1_1") (pintype "passive"))
      (node (ref "VT13") (pin "1") (pinfunction "G_1") (pintype "passive"))
    )
    (net (code "96") (name "unconnected-(R60-Pad1)") (class "Default")
      (node (ref "R60") (pin "1") (pinfunction "1_1") (pintype "passive"))
    )
    (net (code "97") (name "unconnected-(R60-Pad5)") (class "Default")
      (node (ref "R60") (pin "5") (pinfunction "5_5") (pintype "passive"))
    )
    (net (code "98") (name "unconnected-(R84-Pad4)") (class "Default")
      (node (ref "R84") (pin "4") (pinfunction "4_4") (pintype "passive"))
    )
    (net (code "99") (name "unconnected-(R84-Pad8)") (class "Default")
      (node (ref "R84") (pin "8") (pinfunction "8_8") (pintype "passive"))
    )
    (net (code "100") (name "unconnected-(U19-DRAIN0-Pad3)") (class "Default")
      (node (ref "U19") (pin "3") (pinfunction "DRAIN0_3") (pintype "passive+no_connect"))
    )
    (net (code "101") (name "unconnected-(U20-DRAIN5-Pad12)") (class "Default")
      (node (ref "U20") (pin "12") (pinfunction "DRAIN5_12") (pintype "passive+no_connect"))
    )
    (net (code "102") (name "unconnected-(U20-DRAIN6-Pad13)") (class "Default")
      (node (ref "U20") (pin "13") (pinfunction "DRAIN6_13") (pintype "passive+no_connect"))
    )
    (net (code "103") (name "unconnected-(U21-DRAIN2-Pad5)") (class "Default")
      (node (ref "U21") (pin "5") (pinfunction "DRAIN2_5") (pintype "passive+no_connect"))
    )
    (net (code "104") (name "unconnected-(U21-DRAIN3-Pad6)") (class "Default")
      (node (ref "U21") (pin "6") (pinfunction "DRAIN3_6") (pintype "passive+no_connect"))
    )
    (net (code "105") (name "unconnected-(U21-DRAIN4-Pad11)") (class "Default")
      (node (ref "U21") (pin "11") (pinfunction "DRAIN4_11") (pintype "passive+no_connect"))
    )
    (net (code "106") (name "unconnected-(U21-DRAIN5-Pad12)") (class "Default")
      (node (ref "U21") (pin "12") (pinfunction "DRAIN5_12") (pintype "passive+no_connect"))
    )
    (net (code "107") (name "unconnected-(U21-DRAIN6-Pad13)") (class "Default")
      (node (ref "U21") (pin "13") (pinfunction "DRAIN6_13") (pintype "passive+no_connect"))
    )
    (net (code "108") (name "unconnected-(U21-DRAIN7-Pad14)") (class "Default")
      (node (ref "U21") (pin "14") (pinfunction "DRAIN7_14") (pintype "passive+no_connect"))
    )
    (net (code "109") (name "unconnected-(U23-QA-Pad15)") (class "Default")
      (node (ref "U23") (pin "15") (pinfunction "QA_15") (pintype "passive+no_connect"))
    )
    (net (code "110") (name "unconnected-(U24-QA-Pad15)") (class "Default")
      (node (ref "U24") (pin "15") (pinfunction "QA_15") (pintype "passive"))
    )
    (net (code "111") (name "unconnected-(U24-QC-Pad2)") (class "Default")
      (node (ref "U24") (pin "2") (pinfunction "QC_2") (pintype "passive+no_connect"))
    )
    (net (code "112") (name "unconnected-(U24-QD-Pad3)") (class "Default")
      (node (ref "U24") (pin "3") (pinfunction "QD_3") (pintype "passive+no_connect"))
    )
  )
)
